# TCRT5000_SMT.net
KiCad netlist of a schematic drawn in Altium Designer
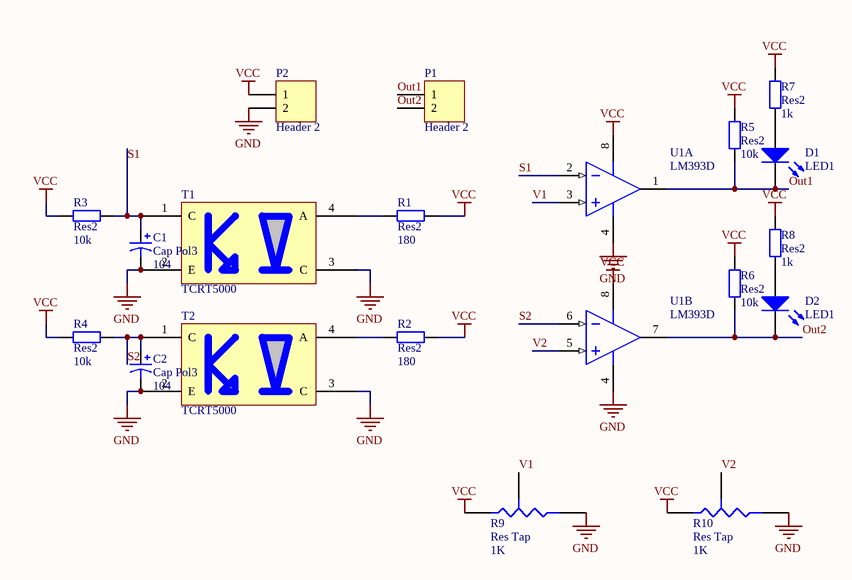
[diagram p0: TCRT5000_SMT.SchDoc]

(export (version "E")
  (design (tool "Eeschema 10.0.6"))
  (components
    (comp (ref "C1")
      (value "Cap Pol3")
      (footprint "0805C")
      (description "Polarized Capacitor (Surface Mount)")
      (fields (field (name "ALTIUM_VALUE") "104") (field (name "PUBLISHER") "Altium Limited"))
      (libsource (lib "Miscellaneous Devices") (part "Cap Pol3"))
    )
    (comp (ref "C2")
      (value "Cap Pol3")
      (footprint "0805C")
      (description "Polarized Capacitor (Surface Mount)")
      (fields (field (name "ALTIUM_VALUE") "104") (field (name "PUBLISHER") "Altium Limited"))
      (libsource (lib "Miscellaneous Devices") (part "Cap Pol3"))
    )
    (comp (ref "D1")
      (value "LED1")
      (footprint "0603L")
      (description "Typical RED GaAs LED")
      (fields (field (name "PUBLISHER") "Altium Limited"))
      (libsource (lib "Miscellaneous Devices") (part "LED1"))
    )
    (comp (ref "D2")
      (value "LED1")
      (footprint "0603L")
      (description "Typical RED GaAs LED")
      (fields (field (name "PUBLISHER") "Altium Limited"))
      (libsource (lib "Miscellaneous Devices") (part "LED1"))
    )
    (comp (ref "P1")
      (value "Header 2")
      (footprint "HDR1X2")
      (description "Header, 2-Pin")
      (fields (field (name "PUBLISHER") "Altium Limited"))
      (libsource (lib "Miscellaneous Connectors") (part "Header 2"))
    )
    (comp (ref "P2")
      (value "Header 2")
      (footprint "HDR1X2")
      (description "Header, 2-Pin")
      (fields (field (name "PUBLISHER") "Altium Limited"))
      (libsource (lib "Miscellaneous Connectors") (part "Header 2"))
    )
    (comp (ref "R1")
      (value "Res2")
      (footprint "0805R")
      (description "Resistor")
      (fields (field (name "ALTIUM_VALUE") "180") (field (name "PUBLISHER") "Altium Limited"))
      (libsource (lib "") (part "Res2_1"))
    )
    (comp (ref "R2")
      (value "Res2")
      (footprint "0805R")
      (description "Resistor")
      (fields (field (name "ALTIUM_VALUE") "180") (field (name "PUBLISHER") "Altium Limited"))
      (libsource (lib "") (part "Res2_1"))
    )
    (comp (ref "R3")
      (value "Res2")
      (footprint "0805R")
      (description "Resistor")
      (fields (field (name "ALTIUM_VALUE") "10k") (field (name "PUBLISHER") "Altium Limited"))
      (libsource (lib "") (part "Res2_1"))
    )
    (comp (ref "R4")
      (value "Res2")
      (footprint "0805R")
      (description "Resistor")
      (fields (field (name "ALTIUM_VALUE") "10k") (field (name "PUBLISHER") "Altium Limited"))
      (libsource (lib "") (part "Res2_1"))
    )
    (comp (ref "R5")
      (value "Res2")
      (footprint "0805R")
      (description "Resistor")
      (fields (field (name "ALTIUM_VALUE") "10k") (field (name "PUBLISHER") "Altium Limited"))
      (libsource (lib "Miscellaneous Devices") (part "Res2"))
    )
    (comp (ref "R6")
      (value "Res2")
      (footprint "0805R")
      (description "Resistor")
      (fields (field (name "ALTIUM_VALUE") "10k") (field (name "PUBLISHER") "Altium Limited"))
      (libsource (lib "Miscellaneous Devices") (part "Res2"))
    )
    (comp (ref "R7")
      (value "Res2")
      (footprint "0805R")
      (description "Resistor")
      (fields (field (name "ALTIUM_VALUE") "1k") (field (name "PUBLISHER") "Altium Limited"))
      (libsource (lib "Miscellaneous Devices") (part "Res2"))
    )
    (comp (ref "R8")
      (value "Res2")
      (footprint "0805R")
      (description "Resistor")
      (fields (field (name "ALTIUM_VALUE") "1k") (field (name "PUBLISHER") "Altium Limited"))
      (libsource (lib "Miscellaneous Devices") (part "Res2"))
    )
    (comp (ref "R9")
      (value "Res Tap")
      (footprint "VR4-2")
      (description "Tapped Resistor")
      (fields (field (name "ALTIUM_VALUE") "1K") (field (name "PUBLISHER") "Altium Limited"))
      (libsource (lib "Miscellaneous Devices") (part "Res Tap"))
    )
    (comp (ref "R10")
      (value "Res Tap")
      (footprint "VR4-2")
      (description "Tapped Resistor")
      (fields (field (name "ALTIUM_VALUE") "1K") (field (name "PUBLISHER") "Altium Limited"))
      (libsource (lib "Miscellaneous Devices") (part "Res Tap"))
    )
    (comp (ref "T1") (value "TCRT5000") (footprint "DIP-4N") (libsource (lib "TCRT5000") (part "TCRT5000")))
    (comp (ref "T2") (value "TCRT5000") (footprint "DIP-4N") (libsource (lib "TCRT5000") (part "TCRT5000")))
    (comp (ref "U1")
      (value "LM393D")
      (footprint "SO8_N")
      (description "Low-Power Dual Voltage Comparator")
      (fields (field (name "PUBLISHER") "Altium Limited"))
      (libsource (lib "ST Analog Comparator") (part "LM393D"))
    )
  )
  (nets
    (net (code "1") (name "/Out1") (class "Default")
      (node (ref "D1") (pin "2") (pinfunction "K_2") (pintype "passive"))
      (node (ref "P1") (pin "1") (pinfunction "1_1") (pintype "passive"))
      (node (ref "R5") (pin "2") (pinfunction "2_2") (pintype "passive"))
      (node (ref "U1") (pin "1") (pinfunction "OUT_1") (pintype "open_collector"))
    )
    (net (code "2") (name "/Out2") (class "Default")
      (node (ref "D2") (pin "2") (pinfunction "K_2") (pintype "passive"))
      (node (ref "P1") (pin "2") (pinfunction "2_2") (pintype "passive"))
      (node (ref "R6") (pin "2") (pinfunction "2_2") (pintype "passive"))
      (node (ref "U1") (pin "7") (pinfunction "OUT_7") (pintype "open_collector"))
    )
    (net (code "3") (name "/S1") (class "Default")
      (node (ref "C1") (pin "1") (pinfunction "1_1") (pintype "passive"))
      (node (ref "R3") (pin "2") (pinfunction "2_2") (pintype "passive"))
      (node (ref "T1") (pin "1") (pinfunction "C_1") (pintype "passive"))
      (node (ref "U1") (pin "2") (pinfunction "IN-_2") (pintype "input"))
    )
    (net (code "4") (name "/S2") (class "Default")
      (node (ref "C2") (pin "1") (pinfunction "1_1") (pintype "passive"))
      (node (ref "R4") (pin "2") (pinfunction "2_2") (pintype "passive"))
      (node (ref "T2") (pin "1") (pinfunction "C_1") (pintype "passive"))
      (node (ref "U1") (pin "6") (pinfunction "IN-_6") (pintype "input"))
    )
    (net (code "5") (name "/V1") (class "Default")
      (node (ref "R9") (pin "3") (pinfunction "TAP_3") (pintype "passive"))
      (node (ref "U1") (pin "3") (pinfunction "IN+_3") (pintype "input"))
    )
    (net (code "6") (name "/V2") (class "Default")
      (node (ref "R10") (pin "3") (pinfunction "TAP_3") (pintype "passive"))
      (node (ref "U1") (pin "5") (pinfunction "IN+_5") (pintype "input"))
    )
    (net (code "7") (name "GND") (class "Default")
      (node (ref "C1") (pin "2") (pinfunction "2_2") (pintype "passive"))
      (node (ref "C2") (pin "2") (pinfunction "2_2") (pintype "passive"))
      (node (ref "P2") (pin "2") (pinfunction "2_2") (pintype "passive"))
      (node (ref "R10") (pin "2") (pinfunction "B_2") (pintype "passive"))
      (node (ref "R9") (pin "2") (pinfunction "B_2") (pintype "passive"))
      (node (ref "T1") (pin "2") (pinfunction "E_2") (pintype "passive"))
      (node (ref "T1") (pin "3") (pinfunction "C_3") (pintype "passive"))
      (node (ref "T2") (pin "2") (pinfunction "E_2") (pintype "passive"))
      (node (ref "T2") (pin "3") (pinfunction "C_3") (pintype "passive"))
      (node (ref "U1") (pin "4") (pinfunction "V-_4") (pintype "power_in"))
    )
    (net (code "8") (name "Net-(D1-A)") (class "Default")
      (node (ref "D1") (pin "1") (pinfunction "A_1") (pintype "passive"))
      (node (ref "R7") (pin "2") (pinfunction "2_2") (pintype "passive"))
    )
    (net (code "9") (name "Net-(D2-A)") (class "Default")
      (node (ref "D2") (pin "1") (pinfunction "A_1") (pintype "passive"))
      (node (ref "R8") (pin "2") (pinfunction "2_2") (pintype "passive"))
    )
    (net (code "10") (name "Net-(T1-A)") (class "Default")
      (node (ref "R1") (pin "1") (pinfunction "1_1") (pintype "passive"))
      (node (ref "T1") (pin "4") (pinfunction "A_4") (pintype "passive"))
    )
    (net (code "11") (name "Net-(T2-A)") (class "Default")
      (node (ref "R2") (pin "1") (pinfunction "1_1") (pintype "passive"))
      (node (ref "T2") (pin "4") (pinfunction "A_4") (pintype "passive"))
    )
    (net (code "12") (name "VCC") (class "Default")
      (node (ref "P2") (pin "1") (pinfunction "1_1") (pintype "passive"))
      (node (ref "R1") (pin "2") (pinfunction "2_2") (pintype "passive"))
      (node (ref "R10") (pin "1") (pinfunction "A_1") (pintype "passive"))
      (node (ref "R2") (pin "2") (pinfunction "2_2") (pintype "passive"))
      (node (ref "R3") (pin "1") (pinfunction "1_1") (pintype "passive"))
      (node (ref "R4") (pin "1") (pinfunction "1_1") (pintype "passive"))
      (node (ref "R5") (pin "1") (pinfunction "1_1") (pintype "passive"))
      (node (ref "R6") (pin "1") (pinfunction "1_1") (pintype "passive"))
      (node (ref "R7") (pin "1") (pinfunction "1_1") (pintype "passive"))
      (node (ref "R8") (pin "1") (pinfunction "1_1") (pintype "passive"))
      (node (ref "R9") (pin "1") (pinfunction "A_1") (pintype "passive"))
      (node (ref "U1") (pin "8") (pinfunction "V+_8") (pintype "power_in"))
    )
  )
)
